# Pluvion_2.net
KiCad netlist of a schematic drawn in EAGLE
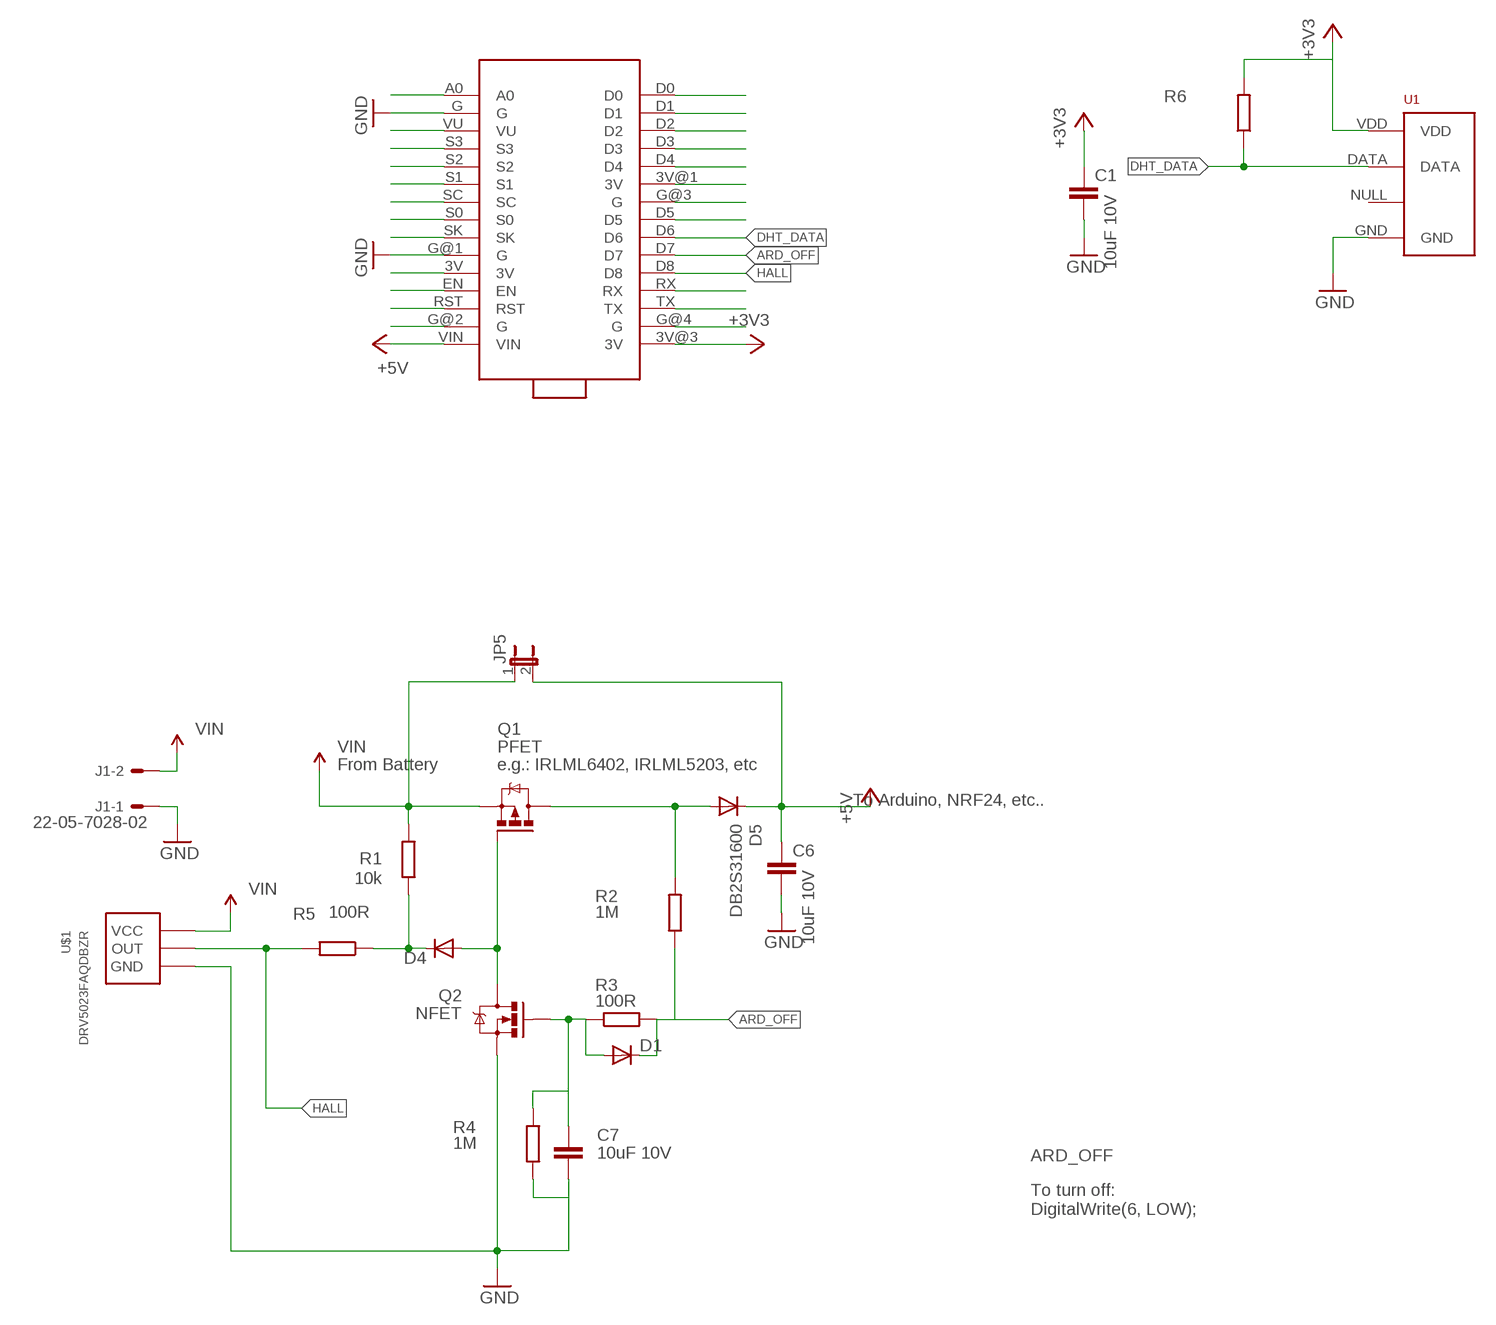
[diagram p0: schematic, sheet 1]

(export (version "E")
  (design (tool "Eeschema 10.0.6"))
  (components
    (comp (ref "C1")
      (value "10uF 10V")
      (footprint "eagle-import:C0805")
      (libsource (lib "eagle-import") (part "C-EUC0805"))
    )
    (comp (ref "C6")
      (value "10uF 10V")
      (footprint "eagle-import:C0805")
      (libsource (lib "eagle-import") (part "C-EUC0805"))
    )
    (comp (ref "C7")
      (value "10uF 10V")
      (footprint "eagle-import:C0805")
      (libsource (lib "eagle-import") (part "C-EUC0805"))
    )
    (comp (ref "D1")
      (value "DIODESOD")
      (footprint "eagle-import:SOD-323")
      (libsource (lib "eagle-import") (part "DIODESOD"))
    )
    (comp (ref "D4")
      (value "DIODESOD")
      (footprint "eagle-import:SOD-323")
      (libsource (lib "eagle-import") (part "DIODESOD"))
    )
    (comp (ref "D5")
      (value "DB2S31600")
      (footprint "eagle-import:SMA-DIODE")
      (libsource (lib "eagle-import") (part "DIODESMA"))
    )
    (comp (ref "J1")
      (value "22-05-7028-02")
      (footprint "eagle-import:7395-02")
      (libsource (lib "eagle-import") (part "22-?-0205-7028"))
    )
    (comp (ref "JP5")
      (value "JUMPER-2PTH")
      (footprint "eagle-import:1X02")
      (libsource (lib "eagle-import") (part "JUMPER-2PTH"))
    )
    (comp (ref "Q1")
      (value "PFET")
      (footprint "eagle-import:MICRO3")
      (libsource (lib "eagle-import") (part "IRLML5203"))
    )
    (comp (ref "Q2")
      (value "NFET")
      (footprint "eagle-import:SOT23")
      (libsource (lib "eagle-import") (part "MOSFET-NCHANNELBSS123LT1G"))
    )
    (comp (ref "R1")
      (value "10k")
      (footprint "eagle-import:R0805")
      (libsource (lib "eagle-import") (part "R-EU_R0805"))
    )
    (comp (ref "R2")
      (value "1M")
      (footprint "eagle-import:R0805")
      (libsource (lib "eagle-import") (part "R-EU_R0805"))
    )
    (comp (ref "R3")
      (value "100R")
      (footprint "eagle-import:R0805")
      (libsource (lib "eagle-import") (part "R-EU_R0805"))
    )
    (comp (ref "R4")
      (value "1M")
      (footprint "eagle-import:R0805")
      (libsource (lib "eagle-import") (part "R-EU_R0805"))
    )
    (comp (ref "R5")
      (value "100R")
      (footprint "eagle-import:R0805")
      (libsource (lib "eagle-import") (part "R-EU_R0805"))
    )
    (comp (ref "R6")
      (value "R-EU_R0805")
      (footprint "eagle-import:R0805")
      (libsource (lib "eagle-import") (part "R-EU_R0805"))
    )
    (comp (ref "U$1")
      (value "DRV5023FAQDBZR")
      (footprint "eagle-import:SOT23")
      (libsource (lib "eagle-import") (part "DRV5023FAQDBZR"))
    )
    (comp (ref "U$2")
      (value "NODE-LOLIN-ESP8266")
      (footprint "eagle-import:NODE-LOLIN-ESP8266")
      (libsource (lib "eagle-import") (part "NODE-LOLIN-ESP8266"))
    )
    (comp (ref "U1")
      (value "RHT03_DHT-22_AM2302RA")
      (footprint "eagle-import:RHT03_DHT-22_RA")
      (libsource (lib "eagle-import") (part "RHT03_DHT-22_AM2302RA"))
    )
  )
  (nets
    (net (code "1") (name "+3V3") (class "Default")
      (node (ref "C1") (pin "1") (pinfunction "1_1") (pintype "passive"))
      (node (ref "R6") (pin "2") (pinfunction "2_2") (pintype "passive"))
      (node (ref "U$2") (pin "3V@3") (pinfunction "3V_3V@3") (pintype "bidirectional"))
      (node (ref "U1") (pin "VDD") (pinfunction "VDD_VDD") (pintype "power_in"))
    )
    (net (code "2") (name "+5V") (class "Default")
      (node (ref "C6") (pin "1") (pinfunction "1_1") (pintype "passive"))
      (node (ref "D5") (pin "C") (pinfunction "C_C") (pintype "passive"))
      (node (ref "JP5") (pin "2") (pinfunction "2_2") (pintype "passive"))
      (node (ref "U$2") (pin "VIN") (pinfunction "VIN_VIN") (pintype "bidirectional"))
    )
    (net (code "3") (name "ARD_OFF") (class "Default")
      (node (ref "D1") (pin "1") (pinfunction "C_1") (pintype "passive"))
      (node (ref "R2") (pin "1") (pinfunction "1_1") (pintype "passive"))
      (node (ref "R3") (pin "2") (pinfunction "2_2") (pintype "passive"))
      (node (ref "U$2") (pin "D7") (pinfunction "D7_D7") (pintype "bidirectional"))
    )
    (net (code "4") (name "DHT_DATA") (class "Default")
      (node (ref "R6") (pin "1") (pinfunction "1_1") (pintype "passive"))
      (node (ref "U$2") (pin "D6") (pinfunction "D6_D6") (pintype "bidirectional"))
      (node (ref "U1") (pin "DATA") (pinfunction "DATA_DATA") (pintype "bidirectional"))
    )
    (net (code "5") (name "GND") (class "Default")
      (node (ref "C1") (pin "2") (pinfunction "2_2") (pintype "passive"))
      (node (ref "C6") (pin "2") (pinfunction "2_2") (pintype "passive"))
      (node (ref "C7") (pin "2") (pinfunction "2_2") (pintype "passive"))
      (node (ref "J1") (pin "1") (pinfunction "S_1") (pintype "passive"))
      (node (ref "Q2") (pin "2") (pinfunction "S_2") (pintype "passive"))
      (node (ref "R4") (pin "1") (pinfunction "1_1") (pintype "passive"))
      (node (ref "U$1") (pin "3") (pinfunction "GND_3") (pintype "bidirectional"))
      (node (ref "U$2") (pin "G") (pinfunction "G_G") (pintype "bidirectional"))
      (node (ref "U$2") (pin "G@1") (pinfunction "G_G@1") (pintype "bidirectional"))
      (node (ref "U1") (pin "GND") (pinfunction "GND_GND") (pintype "power_in"))
    )
    (net (code "6") (name "HALL") (class "Default")
      (node (ref "R5") (pin "2") (pinfunction "2_2") (pintype "passive"))
      (node (ref "U$1") (pin "2") (pinfunction "OUT_2") (pintype "bidirectional"))
      (node (ref "U$2") (pin "D8") (pinfunction "D8_D8") (pintype "bidirectional"))
    )
    (net (code "7") (name "Net-(D1-A)") (class "Default")
      (node (ref "C7") (pin "1") (pinfunction "1_1") (pintype "passive"))
      (node (ref "D1") (pin "2") (pinfunction "A_2") (pintype "passive"))
      (node (ref "Q2") (pin "1") (pinfunction "G_1") (pintype "passive"))
      (node (ref "R3") (pin "1") (pinfunction "1_1") (pintype "passive"))
      (node (ref "R4") (pin "2") (pinfunction "2_2") (pintype "passive"))
    )
    (net (code "8") (name "Net-(D4-A)") (class "Default")
      (node (ref "D4") (pin "2") (pinfunction "A_2") (pintype "passive"))
      (node (ref "Q1") (pin "1") (pinfunction "G_1") (pintype "passive"))
      (node (ref "Q2") (pin "3") (pinfunction "D_3") (pintype "passive"))
    )
    (net (code "9") (name "Net-(D4-C)") (class "Default")
      (node (ref "D4") (pin "1") (pinfunction "C_1") (pintype "passive"))
      (node (ref "R1") (pin "1") (pinfunction "1_1") (pintype "passive"))
      (node (ref "R5") (pin "1") (pinfunction "1_1") (pintype "passive"))
    )
    (net (code "10") (name "Net-(Q1-D)") (class "Default")
      (node (ref "D5") (pin "A") (pinfunction "A_A") (pintype "passive"))
      (node (ref "Q1") (pin "3") (pinfunction "D_3") (pintype "passive"))
      (node (ref "R2") (pin "2") (pinfunction "2_2") (pintype "passive"))
    )
    (net (code "11") (name "VIN") (class "Default")
      (node (ref "J1") (pin "2") (pinfunction "S_2") (pintype "passive"))
      (node (ref "JP5") (pin "1") (pinfunction "1_1") (pintype "passive"))
      (node (ref "Q1") (pin "2") (pinfunction "S_2") (pintype "passive"))
      (node (ref "R1") (pin "2") (pinfunction "2_2") (pintype "passive"))
      (node (ref "U$1") (pin "1") (pinfunction "VCC_1") (pintype "bidirectional"))
    )
    (net (code "12") (name "unconnected-(U$2-3V-Pad3V@1)") (class "Default")
      (node (ref "U$2") (pin "3V@1") (pinfunction "3V_3V@1") (pintype "bidirectional"))
    )
    (net (code "13") (name "unconnected-(U$2-G-PadG@2)") (class "Default")
      (node (ref "U$2") (pin "G@2") (pinfunction "G_G@2") (pintype "bidirectional"))
    )
    (net (code "14") (name "unconnected-(U$2-G-PadG@3)") (class "Default")
      (node (ref "U$2") (pin "G@3") (pinfunction "G_G@3") (pintype "bidirectional"))
    )
    (net (code "15") (name "unconnected-(U$2-G-PadG@4)") (class "Default")
      (node (ref "U$2") (pin "G@4") (pinfunction "G_G@4") (pintype "bidirectional"))
    )
    (net (code "16") (name "unconnected-(U$2-Pad3V)") (class "Default")
      (node (ref "U$2") (pin "3V") (pinfunction "3V_3V") (pintype "bidirectional"))
    )
    (net (code "17") (name "unconnected-(U$2-PadA0)") (class "Default")
      (node (ref "U$2") (pin "A0") (pinfunction "A0_A0") (pintype "bidirectional"))
    )
    (net (code "18") (name "unconnected-(U$2-PadD0)") (class "Default")
      (node (ref "U$2") (pin "D0") (pinfunction "D0_D0") (pintype "bidirectional"))
    )
    (net (code "19") (name "unconnected-(U$2-PadD1)") (class "Default")
      (node (ref "U$2") (pin "D1") (pinfunction "D1_D1") (pintype "bidirectional"))
    )
    (net (code "20") (name "unconnected-(U$2-PadD2)") (class "Default")
      (node (ref "U$2") (pin "D2") (pinfunction "D2_D2") (pintype "bidirectional"))
    )
    (net (code "21") (name "unconnected-(U$2-PadD3)") (class "Default")
      (node (ref "U$2") (pin "D3") (pinfunction "D3_D3") (pintype "bidirectional"))
    )
    (net (code "22") (name "unconnected-(U$2-PadD4)") (class "Default")
      (node (ref "U$2") (pin "D4") (pinfunction "D4_D4") (pintype "bidirectional"))
    )
    (net (code "23") (name "unconnected-(U$2-PadD5)") (class "Default")
      (node (ref "U$2") (pin "D5") (pinfunction "D5_D5") (pintype "bidirectional"))
    )
    (net (code "24") (name "unconnected-(U$2-PadEN)") (class "Default")
      (node (ref "U$2") (pin "EN") (pinfunction "EN_EN") (pintype "bidirectional"))
    )
    (net (code "25") (name "unconnected-(U$2-PadRST)") (class "Default")
      (node (ref "U$2") (pin "RST") (pinfunction "RST_RST") (pintype "bidirectional"))
    )
    (net (code "26") (name "unconnected-(U$2-PadRX)") (class "Default")
      (node (ref "U$2") (pin "RX") (pinfunction "RX_RX") (pintype "bidirectional"))
    )
    (net (code "27") (name "unconnected-(U$2-PadS0)") (class "Default")
      (node (ref "U$2") (pin "S0") (pinfunction "S0_S0") (pintype "bidirectional"))
    )
    (net (code "28") (name "unconnected-(U$2-PadS1)") (class "Default")
      (node (ref "U$2") (pin "S1") (pinfunction "S1_S1") (pintype "bidirectional"))
    )
    (net (code "29") (name "unconnected-(U$2-PadS2)") (class "Default")
      (node (ref "U$2") (pin "S2") (pinfunction "S2_S2") (pintype "bidirectional"))
    )
    (net (code "30") (name "unconnected-(U$2-PadS3)") (class "Default")
      (node (ref "U$2") (pin "S3") (pinfunction "S3_S3") (pintype "bidirectional"))
    )
    (net (code "31") (name "unconnected-(U$2-PadSC)") (class "Default")
      (node (ref "U$2") (pin "SC") (pinfunction "SC_SC") (pintype "bidirectional"))
    )
    (net (code "32") (name "unconnected-(U$2-PadSK)") (class "Default")
      (node (ref "U$2") (pin "SK") (pinfunction "SK_SK") (pintype "bidirectional"))
    )
    (net (code "33") (name "unconnected-(U$2-PadTX)") (class "Default")
      (node (ref "U$2") (pin "TX") (pinfunction "TX_TX") (pintype "bidirectional"))
    )
    (net (code "34") (name "unconnected-(U$2-PadVU)") (class "Default")
      (node (ref "U$2") (pin "VU") (pinfunction "VU_VU") (pintype "bidirectional"))
    )
    (net (code "35") (name "unconnected-(U1-PadNULL)") (class "Default")
      (node (ref "U1") (pin "NULL") (pinfunction "NULL_NULL") (pintype "no_connect"))
    )
  )
)
